# FTDIMicro.net
KiCad netlist of a schematic drawn in EAGLE
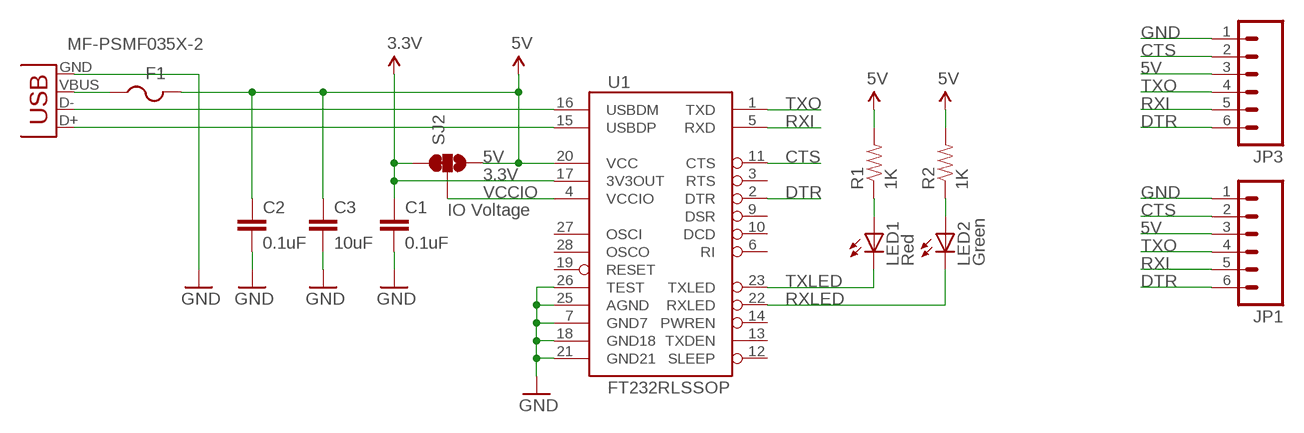
[diagram p0: schematic, sheet 1]

(export (version "E")
  (design (tool "Eeschema 10.0.6"))
  (components
    (comp (ref "C1")
      (value "0.1uF")
      (footprint "eagle-import:0603-CAP")
      (libsource (lib "eagle-import") (part "CAP0603-CAP"))
    )
    (comp (ref "C2")
      (value "0.1uF")
      (footprint "eagle-import:0603-CAP")
      (libsource (lib "eagle-import") (part "CAP0603-CAP"))
    )
    (comp (ref "C3")
      (value "10uF")
      (footprint "eagle-import:0603-CAP")
      (libsource (lib "eagle-import") (part "CAP0603-CAP"))
    )
    (comp (ref "F1")
      (value "MF-PSMF035X-2")
      (footprint "eagle-import:R1206")
      (libsource (lib "eagle-import") (part "PTCFUSE-1206"))
    )
    (comp (ref "JP1")
      (value "M06SMD-FEMALE-V2")
      (footprint "eagle-import:1X06-SMD-FEMALE-V2")
      (libsource (lib "eagle-import") (part "M06SMD-FEMALE-V2"))
    )
    (comp (ref "JP3")
      (value "M06SMD-FEMALE-V2")
      (footprint "eagle-import:1X06-SMD-FEMALE-V2")
      (libsource (lib "eagle-import") (part "M06SMD-FEMALE-V2"))
    )
    (comp (ref "LED1")
      (value "Red")
      (footprint "eagle-import:LED-0603")
      (libsource (lib "eagle-import") (part "LED0603"))
    )
    (comp (ref "LED2")
      (value "Green")
      (footprint "eagle-import:LED-0603")
      (libsource (lib "eagle-import") (part "LED0603"))
    )
    (comp (ref "R1")
      (value "1K")
      (footprint "eagle-import:0603-RES")
      (libsource (lib "eagle-import") (part "RESISTOR0603-RES"))
    )
    (comp (ref "R2")
      (value "1K")
      (footprint "eagle-import:0603-RES")
      (libsource (lib "eagle-import") (part "RESISTOR0603-RES"))
    )
    (comp (ref "SJ2")
      (value "SOLDERJUMPER_2WAYS")
      (footprint "eagle-import:SJ_3")
      (libsource (lib "eagle-import") (part "SOLDERJUMPER_2WAYS"))
    )
    (comp (ref "U1")
      (value "FT232RLSSOP")
      (footprint "eagle-import:SSOP28DB")
      (libsource (lib "eagle-import") (part "FT232RLSSOP"))
    )
    (comp (ref "X1")
      (value "USB-MICROB")
      (footprint "eagle-import:USB-MICROB")
      (libsource (lib "eagle-import") (part "USB-MICROB"))
    )
  )
  (nets
    (net (code "1") (name "/CTS") (class "Default")
      (node (ref "JP1") (pin "2") (pinfunction "2_2") (pintype "passive"))
      (node (ref "JP3") (pin "2") (pinfunction "2_2") (pintype "passive"))
      (node (ref "U1") (pin "11") (pinfunction "CTS_11") (pintype "input"))
    )
    (net (code "2") (name "/DTR") (class "Default")
      (node (ref "JP1") (pin "6") (pinfunction "6_6") (pintype "passive"))
      (node (ref "JP3") (pin "6") (pinfunction "6_6") (pintype "passive"))
      (node (ref "U1") (pin "2") (pinfunction "DTR_2") (pintype "output"))
    )
    (net (code "3") (name "/RXI") (class "Default")
      (node (ref "JP1") (pin "5") (pinfunction "5_5") (pintype "passive"))
      (node (ref "JP3") (pin "5") (pinfunction "5_5") (pintype "passive"))
      (node (ref "U1") (pin "5") (pinfunction "RXD_5") (pintype "input"))
    )
    (net (code "4") (name "/RXLED") (class "Default")
      (node (ref "LED2") (pin "C") (pinfunction "C_C") (pintype "passive"))
      (node (ref "U1") (pin "22") (pinfunction "RXLED_22") (pintype "input"))
    )
    (net (code "5") (name "/TXLED") (class "Default")
      (node (ref "LED1") (pin "C") (pinfunction "C_C") (pintype "passive"))
      (node (ref "U1") (pin "23") (pinfunction "TXLED_23") (pintype "input"))
    )
    (net (code "6") (name "/TXO") (class "Default")
      (node (ref "JP1") (pin "4") (pinfunction "4_4") (pintype "passive"))
      (node (ref "JP3") (pin "4") (pinfunction "4_4") (pintype "passive"))
      (node (ref "U1") (pin "1") (pinfunction "TXD_1") (pintype "output"))
    )
    (net (code "7") (name "/VCCIO") (class "Default")
      (node (ref "SJ2") (pin "2") (pinfunction "2_2") (pintype "passive"))
      (node (ref "U1") (pin "4") (pinfunction "VCCIO_4") (pintype "power_in"))
    )
    (net (code "8") (name "3.3V") (class "Default")
      (node (ref "C1") (pin "1") (pinfunction "1_1") (pintype "passive"))
      (node (ref "SJ2") (pin "1") (pinfunction "1_1") (pintype "passive"))
      (node (ref "U1") (pin "17") (pinfunction "3V3OUT_17") (pintype "output"))
    )
    (net (code "9") (name "5V") (class "Default")
      (node (ref "C2") (pin "1") (pinfunction "1_1") (pintype "passive"))
      (node (ref "C3") (pin "1") (pinfunction "1_1") (pintype "passive"))
      (node (ref "F1") (pin "2") (pinfunction "2_2") (pintype "passive"))
      (node (ref "JP1") (pin "3") (pinfunction "3_3") (pintype "passive"))
      (node (ref "JP3") (pin "3") (pinfunction "3_3") (pintype "passive"))
      (node (ref "R1") (pin "2") (pinfunction "2_2") (pintype "passive"))
      (node (ref "R2") (pin "2") (pinfunction "2_2") (pintype "passive"))
      (node (ref "SJ2") (pin "3") (pinfunction "3_3") (pintype "passive"))
      (node (ref "U1") (pin "20") (pinfunction "VCC_20") (pintype "power_in"))
    )
    (net (code "10") (name "GND") (class "Default")
      (node (ref "C1") (pin "2") (pinfunction "2_2") (pintype "passive"))
      (node (ref "C2") (pin "2") (pinfunction "2_2") (pintype "passive"))
      (node (ref "C3") (pin "2") (pinfunction "2_2") (pintype "passive"))
      (node (ref "JP1") (pin "1") (pinfunction "1_1") (pintype "passive"))
      (node (ref "JP3") (pin "1") (pinfunction "1_1") (pintype "passive"))
      (node (ref "U1") (pin "18") (pinfunction "GND18_18") (pintype "power_in"))
      (node (ref "U1") (pin "21") (pinfunction "GND21_21") (pintype "power_in"))
      (node (ref "U1") (pin "25") (pinfunction "AGND_25") (pintype "power_in"))
      (node (ref "U1") (pin "26") (pinfunction "TEST_26") (pintype "input"))
      (node (ref "U1") (pin "7") (pinfunction "GND7_7") (pintype "power_in"))
      (node (ref "X1") (pin "GND") (pinfunction "GND_GND") (pintype "bidirectional"))
    )
    (net (code "11") (name "Net-(F1-Pad1)") (class "Default")
      (node (ref "F1") (pin "1") (pinfunction "1_1") (pintype "passive"))
      (node (ref "X1") (pin "VBUS") (pinfunction "VBUS_VBUS") (pintype "bidirectional"))
    )
    (net (code "12") (name "Net-(LED1-PadA)") (class "Default")
      (node (ref "LED1") (pin "A") (pinfunction "A_A") (pintype "passive"))
      (node (ref "R1") (pin "1") (pinfunction "1_1") (pintype "passive"))
    )
    (net (code "13") (name "Net-(LED2-PadA)") (class "Default")
      (node (ref "LED2") (pin "A") (pinfunction "A_A") (pintype "passive"))
      (node (ref "R2") (pin "1") (pinfunction "1_1") (pintype "passive"))
    )
    (net (code "14") (name "Net-(U1-USBDM)") (class "Default")
      (node (ref "U1") (pin "16") (pinfunction "USBDM_16") (pintype "bidirectional"))
      (node (ref "X1") (pin "D-") (pinfunction "D-_D-") (pintype "bidirectional"))
    )
    (net (code "15") (name "Net-(U1-USBDP)") (class "Default")
      (node (ref "U1") (pin "15") (pinfunction "USBDP_15") (pintype "bidirectional"))
      (node (ref "X1") (pin "D+") (pinfunction "D+_D+") (pintype "bidirectional"))
    )
    (net (code "16") (name "unconnected-(U1-DCD-Pad10)") (class "Default")
      (node (ref "U1") (pin "10") (pinfunction "DCD_10") (pintype "input"))
    )
    (net (code "17") (name "unconnected-(U1-DSR-Pad9)") (class "Default")
      (node (ref "U1") (pin "9") (pinfunction "DSR_9") (pintype "input"))
    )
    (net (code "18") (name "unconnected-(U1-OSCI-Pad27)") (class "Default")
      (node (ref "U1") (pin "27") (pinfunction "OSCI_27") (pintype "input"))
    )
    (net (code "19") (name "unconnected-(U1-OSCO-Pad28)") (class "Default")
      (node (ref "U1") (pin "28") (pinfunction "OSCO_28") (pintype "output"))
    )
    (net (code "20") (name "unconnected-(U1-PWREN-Pad14)") (class "Default")
      (node (ref "U1") (pin "14") (pinfunction "PWREN_14") (pintype "input"))
    )
    (net (code "21") (name "unconnected-(U1-RESET-Pad19)") (class "Default")
      (node (ref "U1") (pin "19") (pinfunction "RESET_19") (pintype "input"))
    )
    (net (code "22") (name "unconnected-(U1-RI-Pad6)") (class "Default")
      (node (ref "U1") (pin "6") (pinfunction "RI_6") (pintype "input"))
    )
    (net (code "23") (name "unconnected-(U1-RTS-Pad3)") (class "Default")
      (node (ref "U1") (pin "3") (pinfunction "RTS_3") (pintype "output"))
    )
    (net (code "24") (name "unconnected-(U1-SLEEP-Pad12)") (class "Default")
      (node (ref "U1") (pin "12") (pinfunction "SLEEP_12") (pintype "input"))
    )
    (net (code "25") (name "unconnected-(U1-TXDEN-Pad13)") (class "Default")
      (node (ref "U1") (pin "13") (pinfunction "TXDEN_13") (pintype "input"))
    )
  )
)
